# rad_detector_v500_ANA.net
KiCad netlist of a schematic drawn in Altium Designer
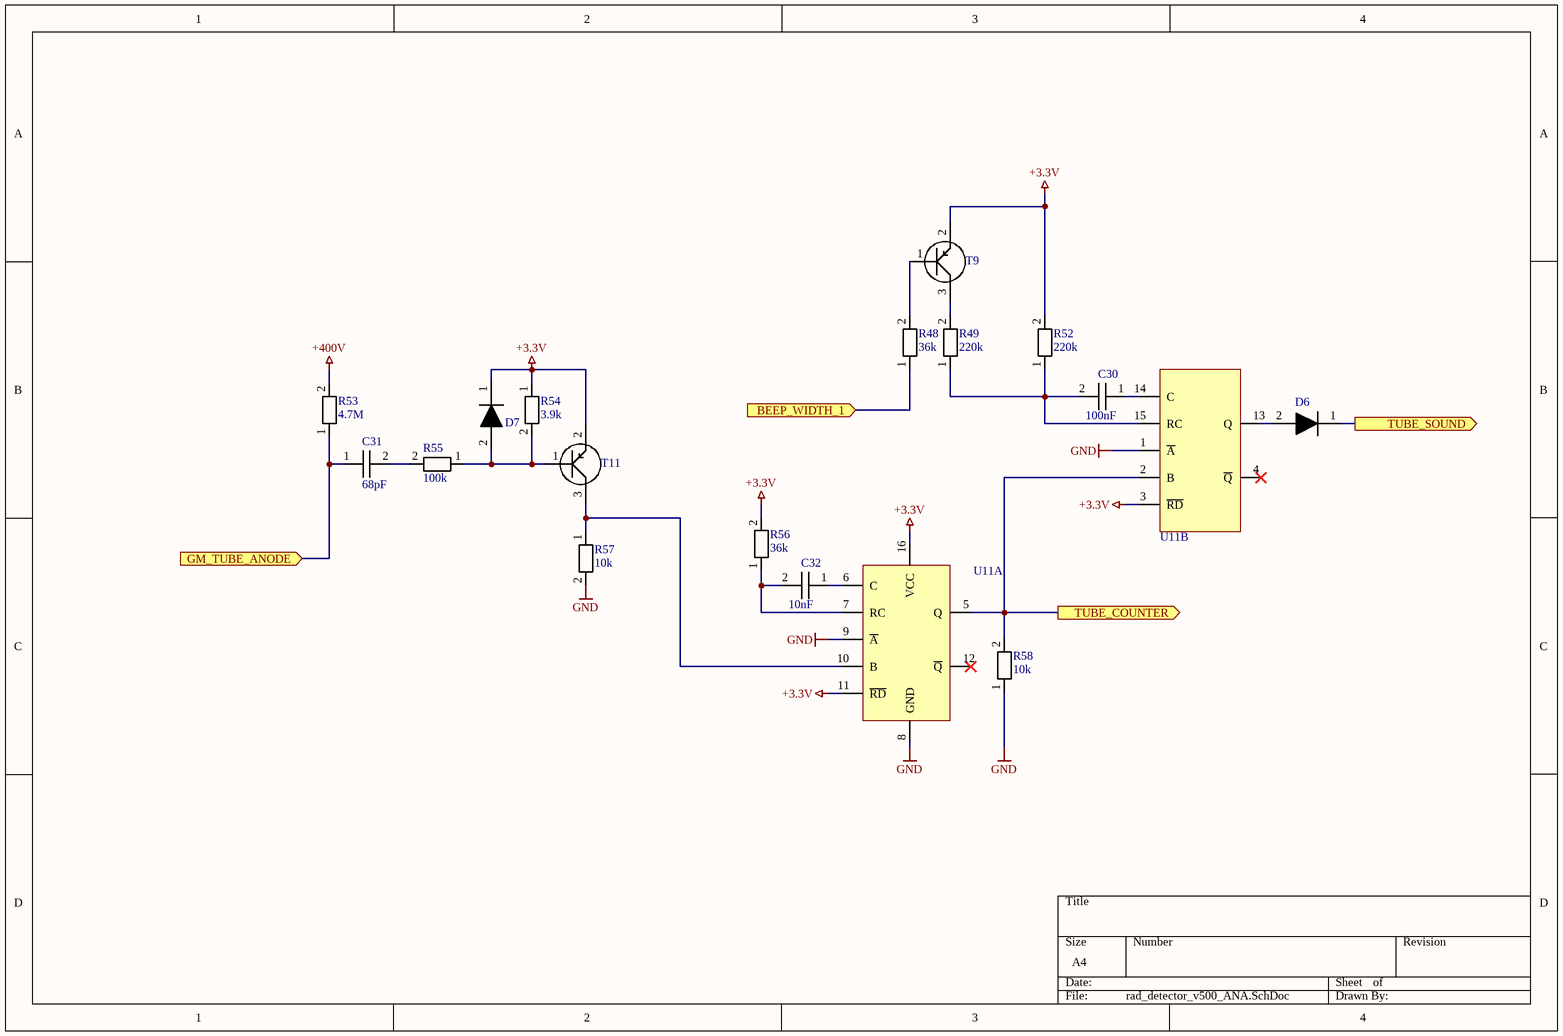
[diagram p0: rad_detector_v500_ANA.SchDoc]

(export (version "E")
  (design (tool "Eeschema 10.0.6"))
  (components
    (comp (ref "C30") (value "100nF") (footprint "0805_C") (libsource (lib "Schlib1") (part "CAPACITOR")))
    (comp (ref "C31")
      (value "68pF")
      (footprint "CAPACITOR_250MIL")
      (libsource (lib "Schlib1") (part "CAPACITOR"))
    )
    (comp (ref "C32") (value "10nF") (footprint "0805_C") (libsource (lib "Schlib1") (part "CAPACITOR")))
    (comp (ref "D6") (value "DIODE") (footprint "SMD_DIODE_SOD80") (libsource (lib "Schlib1") (part "DIODE")))
    (comp (ref "D7") (value "DIODE") (footprint "SMD_DIODE_SOD80") (libsource (lib "Schlib1") (part "DIODE")))
    (comp (ref "R48") (value "36k") (footprint "0805") (libsource (lib "Schlib1") (part "RESISTOR")))
    (comp (ref "R49") (value "220k") (footprint "0805") (libsource (lib "Schlib1") (part "RESISTOR")))
    (comp (ref "R52") (value "220k") (footprint "0805") (libsource (lib "Schlib1") (part "RESISTOR")))
    (comp (ref "R53") (value "4.7M") (footprint "0805") (libsource (lib "Schlib1") (part "RESISTOR")))
    (comp (ref "R54") (value "3.9k") (footprint "0805") (libsource (lib "Schlib1") (part "RESISTOR")))
    (comp (ref "R55") (value "100k") (footprint "0805") (libsource (lib "Schlib1") (part "RESISTOR")))
    (comp (ref "R56") (value "36k") (footprint "0805") (libsource (lib "Schlib1") (part "RESISTOR")))
    (comp (ref "R57") (value "10k") (footprint "0805") (libsource (lib "Schlib1") (part "RESISTOR")))
    (comp (ref "R58") (value "10k") (footprint "0805") (libsource (lib "Schlib1") (part "RESISTOR")))
    (comp (ref "T9") (value "BC856") (footprint "SOT23") (libsource (lib "Schlib1") (part "TRANSISTOR_PNP")))
    (comp (ref "T11") (value "BC856") (footprint "SOT23") (libsource (lib "Schlib1") (part "TRANSISTOR_PNP")))
    (comp (ref "U11") (value "74HCT123") (footprint "74HCT123") (libsource (lib "") (part "74HCT123_1")))
  )
  (nets
    (net (code "1") (name "+3.3V") (class "Default")
      (node (ref "D7") (pin "1") (pinfunction "1_1") (pintype "passive"))
      (node (ref "R52") (pin "2") (pinfunction "1_2") (pintype "passive"))
      (node (ref "R54") (pin "1") (pinfunction "0_1") (pintype "passive"))
      (node (ref "R56") (pin "2") (pinfunction "1_2") (pintype "passive"))
      (node (ref "T11") (pin "2") (pinfunction "2_2") (pintype "passive"))
      (node (ref "T9") (pin "2") (pinfunction "2_2") (pintype "passive"))
      (node (ref "U11") (pin "11") (pinfunction "~{RD}_11") (pintype "passive"))
      (node (ref "U11") (pin "16") (pinfunction "VCC_16") (pintype "passive"))
      (node (ref "U11") (pin "3") (pinfunction "~{RD}_3") (pintype "passive"))
    )
    (net (code "2") (name "+400V") (class "Default")
      (node (ref "R53") (pin "2") (pinfunction "1_2") (pintype "passive"))
    )
    (net (code "3") (name "/BEEP_WIDTH_1") (class "Default")
      (node (ref "R48") (pin "1") (pinfunction "0_1") (pintype "passive"))
    )
    (net (code "4") (name "/GM_TUBE_ANODE") (class "Default")
      (node (ref "C31") (pin "1") (pinfunction "1_1") (pintype "passive"))
      (node (ref "R53") (pin "1") (pinfunction "0_1") (pintype "passive"))
    )
    (net (code "5") (name "/TUBE_COUNTER") (class "Default")
      (node (ref "R58") (pin "2") (pinfunction "1_2") (pintype "passive"))
      (node (ref "U11") (pin "2") (pinfunction "B_2") (pintype "passive"))
      (node (ref "U11") (pin "5") (pinfunction "Q_5") (pintype "passive"))
    )
    (net (code "6") (name "/TUBE_SOUND") (class "Default")
      (node (ref "D6") (pin "1") (pinfunction "1_1") (pintype "passive"))
    )
    (net (code "7") (name "GND") (class "Default")
      (node (ref "R57") (pin "2") (pinfunction "1_2") (pintype "passive"))
      (node (ref "R58") (pin "1") (pinfunction "0_1") (pintype "passive"))
      (node (ref "U11") (pin "1") (pinfunction "~{A}_1") (pintype "passive"))
      (node (ref "U11") (pin "8") (pinfunction "GND_8") (pintype "passive"))
      (node (ref "U11") (pin "9") (pinfunction "~{A}_9") (pintype "passive"))
    )
    (net (code "8") (name "Net-(R48-1)") (class "Default")
      (node (ref "R48") (pin "2") (pinfunction "1_2") (pintype "passive"))
      (node (ref "T9") (pin "1") (pinfunction "1_1") (pintype "passive"))
    )
    (net (code "9") (name "Net-(R49-0)") (class "Default")
      (node (ref "C30") (pin "2") (pinfunction "2_2") (pintype "passive"))
      (node (ref "R49") (pin "1") (pinfunction "0_1") (pintype "passive"))
      (node (ref "R52") (pin "1") (pinfunction "0_1") (pintype "passive"))
      (node (ref "U11") (pin "15") (pinfunction "RC_15") (pintype "passive"))
    )
    (net (code "10") (name "Net-(R49-1)") (class "Default")
      (node (ref "R49") (pin "2") (pinfunction "1_2") (pintype "passive"))
      (node (ref "T9") (pin "3") (pinfunction "3_3") (pintype "passive"))
    )
    (net (code "11") (name "Net-(R54-1)") (class "Default")
      (node (ref "D7") (pin "2") (pinfunction "2_2") (pintype "passive"))
      (node (ref "R54") (pin "2") (pinfunction "1_2") (pintype "passive"))
      (node (ref "R55") (pin "1") (pinfunction "0_1") (pintype "passive"))
      (node (ref "T11") (pin "1") (pinfunction "1_1") (pintype "passive"))
    )
    (net (code "12") (name "Net-(R55-1)") (class "Default")
      (node (ref "C31") (pin "2") (pinfunction "2_2") (pintype "passive"))
      (node (ref "R55") (pin "2") (pinfunction "1_2") (pintype "passive"))
    )
    (net (code "13") (name "Net-(R56-0)") (class "Default")
      (node (ref "C32") (pin "2") (pinfunction "2_2") (pintype "passive"))
      (node (ref "R56") (pin "1") (pinfunction "0_1") (pintype "passive"))
      (node (ref "U11") (pin "7") (pinfunction "RC_7") (pintype "passive"))
    )
    (net (code "14") (name "Net-(R57-0)") (class "Default")
      (node (ref "R57") (pin "1") (pinfunction "0_1") (pintype "passive"))
      (node (ref "T11") (pin "3") (pinfunction "3_3") (pintype "passive"))
      (node (ref "U11") (pin "10") (pinfunction "B_10") (pintype "passive"))
    )
    (net (code "15") (name "Net-(U11A-C)") (class "Default")
      (node (ref "C32") (pin "1") (pinfunction "1_1") (pintype "passive"))
      (node (ref "U11") (pin "6") (pinfunction "C_6") (pintype "passive"))
    )
    (net (code "16") (name "Net-(U11B-C)") (class "Default")
      (node (ref "C30") (pin "1") (pinfunction "1_1") (pintype "passive"))
      (node (ref "U11") (pin "14") (pinfunction "C_14") (pintype "passive"))
    )
    (net (code "17") (name "Net-(U11B-Q)") (class "Default")
      (node (ref "D6") (pin "2") (pinfunction "2_2") (pintype "passive"))
      (node (ref "U11") (pin "13") (pinfunction "Q_13") (pintype "passive"))
    )
    (net (code "18") (name "unconnected-(U11A-~{Q}-Pad12)") (class "Default")
      (node (ref "U11") (pin "12") (pinfunction "~{Q}_12") (pintype "passive+no_connect"))
    )
    (net (code "19") (name "unconnected-(U11B-~{Q}-Pad4)") (class "Default")
      (node (ref "U11") (pin "4") (pinfunction "~{Q}_4") (pintype "passive+no_connect"))
    )
  )
)
